# stepper-v1_1.net
KiCad netlist of a schematic drawn in EAGLE
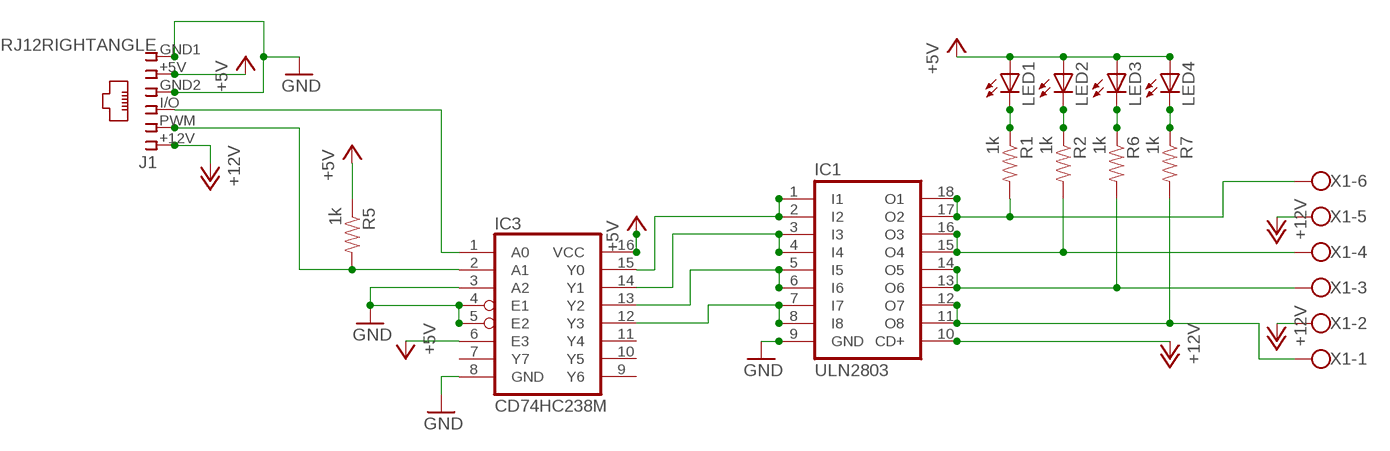
[diagram p0: schematic, sheet 1]

(export (version "E")
  (design (tool "Eeschema 10.0.6"))
  (components
    (comp (ref "IC1")
      (value "ULN2803")
      (footprint "eagle-import:SO18W")
      (libsource (lib "eagle-import") (part "ULN2803A"))
    )
    (comp (ref "IC3")
      (value "CD74HC238M")
      (footprint "eagle-import:SO16")
      (libsource (lib "eagle-import") (part "74238D"))
    )
    (comp (ref "J1")
      (value "RJ12RIGHTANGLE")
      (footprint "eagle-import:RJ12-RIGHTANGLE")
      (libsource (lib "eagle-import") (part "RJ12RIGHTANGLE"))
    )
    (comp (ref "LED1")
      (value "LED3MM")
      (footprint "eagle-import:LED3MM")
      (libsource (lib "eagle-import") (part "LED3MM"))
    )
    (comp (ref "LED2")
      (value "LED3MM")
      (footprint "eagle-import:LED3MM")
      (libsource (lib "eagle-import") (part "LED3MM"))
    )
    (comp (ref "LED3")
      (value "LED3MM")
      (footprint "eagle-import:LED3MM")
      (libsource (lib "eagle-import") (part "LED3MM"))
    )
    (comp (ref "LED4")
      (value "LED3MM")
      (footprint "eagle-import:LED3MM")
      (libsource (lib "eagle-import") (part "LED3MM"))
    )
    (comp (ref "R1")
      (value "1k")
      (footprint "eagle-import:1206")
      (libsource (lib "eagle-import") (part "RESISTOR1206"))
    )
    (comp (ref "R2")
      (value "1k")
      (footprint "eagle-import:1206")
      (libsource (lib "eagle-import") (part "RESISTOR1206"))
    )
    (comp (ref "R5")
      (value "1k")
      (footprint "eagle-import:1206")
      (libsource (lib "eagle-import") (part "RESISTOR1206"))
    )
    (comp (ref "R6")
      (value "1k")
      (footprint "eagle-import:1206")
      (libsource (lib "eagle-import") (part "RESISTOR1206"))
    )
    (comp (ref "R7")
      (value "1k")
      (footprint "eagle-import:1206")
      (libsource (lib "eagle-import") (part "RESISTOR1206"))
    )
    (comp (ref "X1")
      (value "W237-6")
      (footprint "eagle-import:W237-6")
      (libsource (lib "eagle-import") (part "W237-6"))
    )
  )
  (nets
    (net (code "1") (name "+5V") (class "Default")
      (node (ref "IC3") (pin "16") (pinfunction "VCC_16") (pintype "power_in"))
      (node (ref "IC3") (pin "6") (pinfunction "E3_6") (pintype "input"))
      (node (ref "J1") (pin "+5V") (pinfunction "5_+5V") (pintype "bidirectional"))
      (node (ref "LED1") (pin "A") (pinfunction "A_A") (pintype "passive"))
      (node (ref "LED2") (pin "A") (pinfunction "A_A") (pintype "passive"))
      (node (ref "LED3") (pin "A") (pinfunction "A_A") (pintype "passive"))
      (node (ref "LED4") (pin "A") (pinfunction "A_A") (pintype "passive"))
      (node (ref "R5") (pin "1") (pinfunction "1_1") (pintype "passive"))
    )
    (net (code "2") (name "+12V") (class "Default")
      (node (ref "IC1") (pin "10") (pinfunction "CD+_10") (pintype "passive"))
      (node (ref "J1") (pin "+12V") (pinfunction "1_+12V") (pintype "bidirectional"))
      (node (ref "X1") (pin "2") (pinfunction "KL_2") (pintype "passive"))
      (node (ref "X1") (pin "5") (pinfunction "KL_5") (pintype "passive"))
    )
    (net (code "3") (name "GND") (class "Default")
      (node (ref "IC1") (pin "9") (pinfunction "GND_9") (pintype "power_in"))
      (node (ref "IC3") (pin "3") (pinfunction "A2_3") (pintype "input"))
      (node (ref "IC3") (pin "4") (pinfunction "E1_4") (pintype "input"))
      (node (ref "IC3") (pin "5") (pinfunction "E2_5") (pintype "input"))
      (node (ref "IC3") (pin "8") (pinfunction "GND_8") (pintype "power_in"))
      (node (ref "J1") (pin "GND1") (pinfunction "6_GND1") (pintype "bidirectional"))
      (node (ref "J1") (pin "GND2") (pinfunction "4_GND2") (pintype "bidirectional"))
    )
    (net (code "4") (name "Net-(IC1-I1)") (class "Default")
      (node (ref "IC1") (pin "1") (pinfunction "I1_1") (pintype "input"))
      (node (ref "IC1") (pin "2") (pinfunction "I2_2") (pintype "input"))
      (node (ref "IC3") (pin "15") (pinfunction "Y0_15") (pintype "output"))
    )
    (net (code "5") (name "Net-(IC1-I3)") (class "Default")
      (node (ref "IC1") (pin "3") (pinfunction "I3_3") (pintype "input"))
      (node (ref "IC1") (pin "4") (pinfunction "I4_4") (pintype "input"))
      (node (ref "IC3") (pin "14") (pinfunction "Y1_14") (pintype "output"))
    )
    (net (code "6") (name "Net-(IC1-I5)") (class "Default")
      (node (ref "IC1") (pin "5") (pinfunction "I5_5") (pintype "input"))
      (node (ref "IC1") (pin "6") (pinfunction "I6_6") (pintype "input"))
      (node (ref "IC3") (pin "13") (pinfunction "Y2_13") (pintype "output"))
    )
    (net (code "7") (name "Net-(IC1-I7)") (class "Default")
      (node (ref "IC1") (pin "7") (pinfunction "I7_7") (pintype "input"))
      (node (ref "IC1") (pin "8") (pinfunction "I8_8") (pintype "input"))
      (node (ref "IC3") (pin "12") (pinfunction "Y3_12") (pintype "output"))
    )
    (net (code "8") (name "Net-(IC1-O1)") (class "Default")
      (node (ref "IC1") (pin "17") (pinfunction "O2_17") (pintype "open_collector"))
      (node (ref "IC1") (pin "18") (pinfunction "O1_18") (pintype "open_collector"))
      (node (ref "R1") (pin "2") (pinfunction "2_2") (pintype "passive"))
      (node (ref "X1") (pin "6") (pinfunction "KL_6") (pintype "passive"))
    )
    (net (code "9") (name "Net-(IC1-O3)") (class "Default")
      (node (ref "IC1") (pin "15") (pinfunction "O4_15") (pintype "open_collector"))
      (node (ref "IC1") (pin "16") (pinfunction "O3_16") (pintype "open_collector"))
      (node (ref "R2") (pin "2") (pinfunction "2_2") (pintype "passive"))
      (node (ref "X1") (pin "4") (pinfunction "KL_4") (pintype "passive"))
    )
    (net (code "10") (name "Net-(IC1-O5)") (class "Default")
      (node (ref "IC1") (pin "13") (pinfunction "O6_13") (pintype "open_collector"))
      (node (ref "IC1") (pin "14") (pinfunction "O5_14") (pintype "open_collector"))
      (node (ref "R6") (pin "2") (pinfunction "2_2") (pintype "passive"))
      (node (ref "X1") (pin "3") (pinfunction "KL_3") (pintype "passive"))
    )
    (net (code "11") (name "Net-(IC1-O7)") (class "Default")
      (node (ref "IC1") (pin "11") (pinfunction "O8_11") (pintype "open_collector"))
      (node (ref "IC1") (pin "12") (pinfunction "O7_12") (pintype "open_collector"))
      (node (ref "R7") (pin "2") (pinfunction "2_2") (pintype "passive"))
      (node (ref "X1") (pin "1") (pinfunction "KL_1") (pintype "passive"))
    )
    (net (code "12") (name "Net-(IC3-A0)") (class "Default")
      (node (ref "IC3") (pin "1") (pinfunction "A0_1") (pintype "input"))
      (node (ref "J1") (pin "I/O") (pinfunction "3_I/O") (pintype "bidirectional"))
    )
    (net (code "13") (name "Net-(IC3-A1)") (class "Default")
      (node (ref "IC3") (pin "2") (pinfunction "A1_2") (pintype "input"))
      (node (ref "J1") (pin "PWM") (pinfunction "2_PWM") (pintype "bidirectional"))
      (node (ref "R5") (pin "2") (pinfunction "2_2") (pintype "passive"))
    )
    (net (code "14") (name "Net-(LED1-C)") (class "Default")
      (node (ref "LED1") (pin "K") (pinfunction "C_K") (pintype "passive"))
      (node (ref "R1") (pin "1") (pinfunction "1_1") (pintype "passive"))
    )
    (net (code "15") (name "Net-(LED2-C)") (class "Default")
      (node (ref "LED2") (pin "K") (pinfunction "C_K") (pintype "passive"))
      (node (ref "R2") (pin "1") (pinfunction "1_1") (pintype "passive"))
    )
    (net (code "16") (name "Net-(LED3-C)") (class "Default")
      (node (ref "LED3") (pin "K") (pinfunction "C_K") (pintype "passive"))
      (node (ref "R6") (pin "1") (pinfunction "1_1") (pintype "passive"))
    )
    (net (code "17") (name "Net-(LED4-C)") (class "Default")
      (node (ref "LED4") (pin "K") (pinfunction "C_K") (pintype "passive"))
      (node (ref "R7") (pin "1") (pinfunction "1_1") (pintype "passive"))
    )
    (net (code "18") (name "unconnected-(IC3-Y4-Pad11)") (class "Default")
      (node (ref "IC3") (pin "11") (pinfunction "Y4_11") (pintype "output"))
    )
    (net (code "19") (name "unconnected-(IC3-Y5-Pad10)") (class "Default")
      (node (ref "IC3") (pin "10") (pinfunction "Y5_10") (pintype "output"))
    )
    (net (code "20") (name "unconnected-(IC3-Y6-Pad9)") (class "Default")
      (node (ref "IC3") (pin "9") (pinfunction "Y6_9") (pintype "output"))
    )
    (net (code "21") (name "unconnected-(IC3-Y7-Pad7)") (class "Default")
      (node (ref "IC3") (pin "7") (pinfunction "Y7_7") (pintype "output"))
    )
  )
)
